# solderingtest.net
KiCad netlist of a schematic drawn in EAGLE
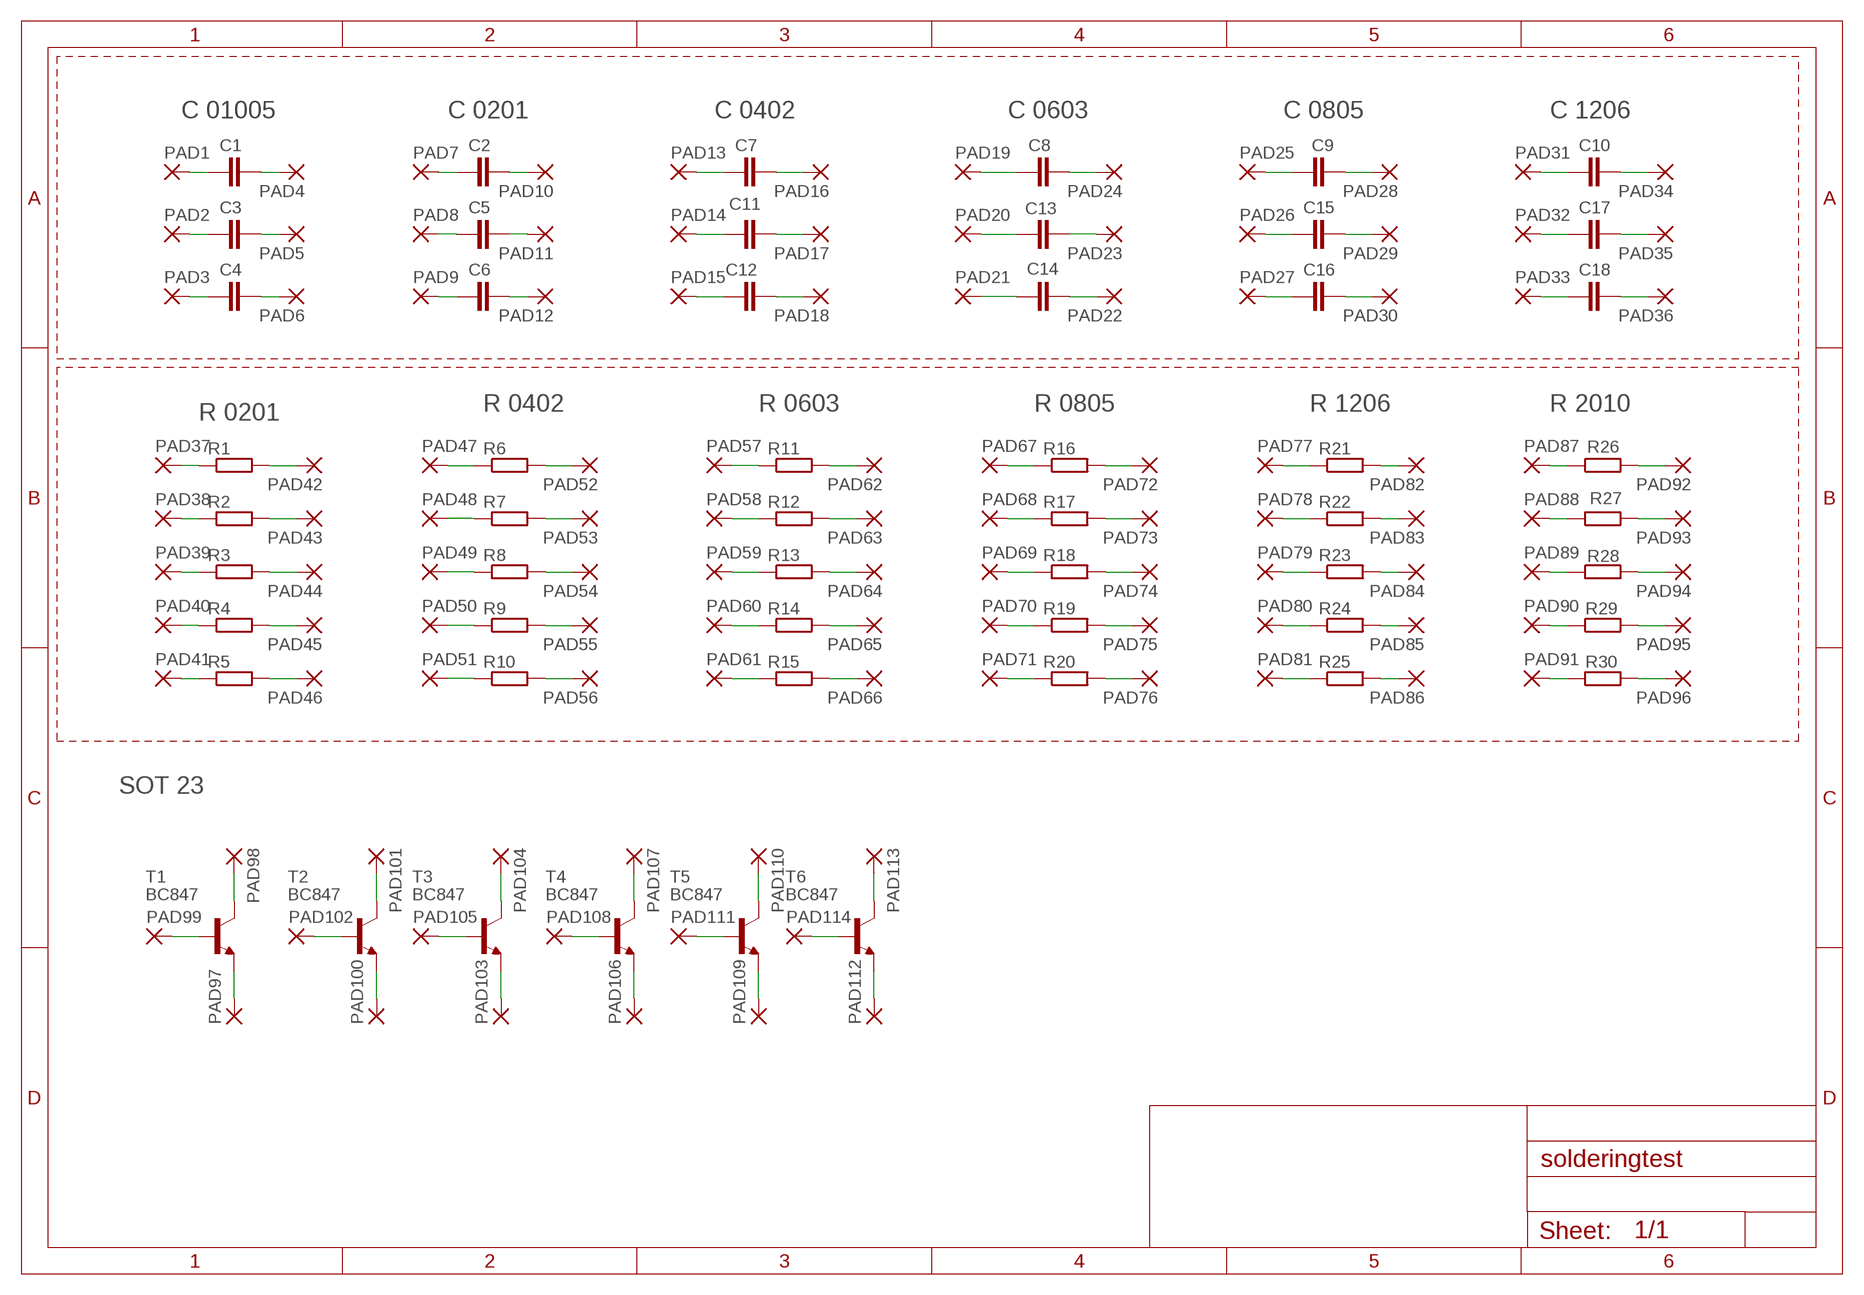
[diagram p0: schematic, sheet 1]

(export (version "E")
  (design (tool "Eeschema 10.0.6"))
  (components
    (comp (ref "C1")
      (value "C-EU01005")
      (footprint "eagle-import:C01005")
      (libsource (lib "eagle-import") (part "C-EU01005"))
    )
    (comp (ref "C2")
      (value "C-EUC0201")
      (footprint "eagle-import:C0201")
      (libsource (lib "eagle-import") (part "C-EUC0201"))
    )
    (comp (ref "C3")
      (value "C-EU01005")
      (footprint "eagle-import:C01005")
      (libsource (lib "eagle-import") (part "C-EU01005"))
    )
    (comp (ref "C4")
      (value "C-EU01005")
      (footprint "eagle-import:C01005")
      (libsource (lib "eagle-import") (part "C-EU01005"))
    )
    (comp (ref "C5")
      (value "C-EUC0201")
      (footprint "eagle-import:C0201")
      (libsource (lib "eagle-import") (part "C-EUC0201"))
    )
    (comp (ref "C6")
      (value "C-EUC0201")
      (footprint "eagle-import:C0201")
      (libsource (lib "eagle-import") (part "C-EUC0201"))
    )
    (comp (ref "C7")
      (value "C-EUC0402")
      (footprint "eagle-import:C0402")
      (libsource (lib "eagle-import") (part "C-EUC0402"))
    )
    (comp (ref "C8")
      (value "C-EUC0603")
      (footprint "eagle-import:C0603")
      (libsource (lib "eagle-import") (part "C-EUC0603"))
    )
    (comp (ref "C9")
      (value "C-EUC0805")
      (footprint "eagle-import:C0805")
      (libsource (lib "eagle-import") (part "C-EUC0805"))
    )
    (comp (ref "C10")
      (value "C-EUC1206")
      (footprint "eagle-import:C1206")
      (libsource (lib "eagle-import") (part "C-EUC1206"))
    )
    (comp (ref "C11")
      (value "C-EUC0402")
      (footprint "eagle-import:C0402")
      (libsource (lib "eagle-import") (part "C-EUC0402"))
    )
    (comp (ref "C12")
      (value "C-EUC0402")
      (footprint "eagle-import:C0402")
      (libsource (lib "eagle-import") (part "C-EUC0402"))
    )
    (comp (ref "C13")
      (value "C-EUC0603")
      (footprint "eagle-import:C0603")
      (libsource (lib "eagle-import") (part "C-EUC0603"))
    )
    (comp (ref "C14")
      (value "C-EUC0603")
      (footprint "eagle-import:C0603")
      (libsource (lib "eagle-import") (part "C-EUC0603"))
    )
    (comp (ref "C15")
      (value "C-EUC0805")
      (footprint "eagle-import:C0805")
      (libsource (lib "eagle-import") (part "C-EUC0805"))
    )
    (comp (ref "C16")
      (value "C-EUC0805")
      (footprint "eagle-import:C0805")
      (libsource (lib "eagle-import") (part "C-EUC0805"))
    )
    (comp (ref "C17")
      (value "C-EUC1206")
      (footprint "eagle-import:C1206")
      (libsource (lib "eagle-import") (part "C-EUC1206"))
    )
    (comp (ref "C18")
      (value "C-EUC1206")
      (footprint "eagle-import:C1206")
      (libsource (lib "eagle-import") (part "C-EUC1206"))
    )
    (comp (ref "PAD1")
      (value "2,54/1,0")
      (footprint "eagle-import:2,54_1,0")
      (libsource (lib "eagle-import") (part "2,54/1,0"))
    )
    (comp (ref "PAD2")
      (value "2,54/1,0")
      (footprint "eagle-import:2,54_1,0")
      (libsource (lib "eagle-import") (part "2,54/1,0"))
    )
    (comp (ref "PAD3")
      (value "2,54/1,0")
      (footprint "eagle-import:2,54_1,0")
      (libsource (lib "eagle-import") (part "2,54/1,0"))
    )
    (comp (ref "PAD4")
      (value "2,54/1,0")
      (footprint "eagle-import:2,54_1,0")
      (libsource (lib "eagle-import") (part "2,54/1,0"))
    )
    (comp (ref "PAD5")
      (value "2,54/1,0")
      (footprint "eagle-import:2,54_1,0")
      (libsource (lib "eagle-import") (part "2,54/1,0"))
    )
    (comp (ref "PAD6")
      (value "2,54/1,0")
      (footprint "eagle-import:2,54_1,0")
      (libsource (lib "eagle-import") (part "2,54/1,0"))
    )
    (comp (ref "PAD7")
      (value "2,54/1,0")
      (footprint "eagle-import:2,54_1,0")
      (libsource (lib "eagle-import") (part "2,54/1,0"))
    )
    (comp (ref "PAD8")
      (value "2,54/1,0")
      (footprint "eagle-import:2,54_1,0")
      (libsource (lib "eagle-import") (part "2,54/1,0"))
    )
    (comp (ref "PAD9")
      (value "2,54/1,0")
      (footprint "eagle-import:2,54_1,0")
      (libsource (lib "eagle-import") (part "2,54/1,0"))
    )
    (comp (ref "PAD10")
      (value "2,54/1,0")
      (footprint "eagle-import:2,54_1,0")
      (libsource (lib "eagle-import") (part "2,54/1,0"))
    )
    (comp (ref "PAD11")
      (value "2,54/1,0")
      (footprint "eagle-import:2,54_1,0")
      (libsource (lib "eagle-import") (part "2,54/1,0"))
    )
    (comp (ref "PAD12")
      (value "2,54/1,0")
      (footprint "eagle-import:2,54_1,0")
      (libsource (lib "eagle-import") (part "2,54/1,0"))
    )
    (comp (ref "PAD13")
      (value "2,54/1,0")
      (footprint "eagle-import:2,54_1,0")
      (libsource (lib "eagle-import") (part "2,54/1,0"))
    )
    (comp (ref "PAD14")
      (value "2,54/1,0")
      (footprint "eagle-import:2,54_1,0")
      (libsource (lib "eagle-import") (part "2,54/1,0"))
    )
    (comp (ref "PAD15")
      (value "2,54/1,0")
      (footprint "eagle-import:2,54_1,0")
      (libsource (lib "eagle-import") (part "2,54/1,0"))
    )
    (comp (ref "PAD16")
      (value "2,54/1,0")
      (footprint "eagle-import:2,54_1,0")
      (libsource (lib "eagle-import") (part "2,54/1,0"))
    )
    (comp (ref "PAD17")
      (value "2,54/1,0")
      (footprint "eagle-import:2,54_1,0")
      (libsource (lib "eagle-import") (part "2,54/1,0"))
    )
    (comp (ref "PAD18")
      (value "2,54/1,0")
      (footprint "eagle-import:2,54_1,0")
      (libsource (lib "eagle-import") (part "2,54/1,0"))
    )
    (comp (ref "PAD19")
      (value "2,54/1,0")
      (footprint "eagle-import:2,54_1,0")
      (libsource (lib "eagle-import") (part "2,54/1,0"))
    )
    (comp (ref "PAD20")
      (value "2,54/1,0")
      (footprint "eagle-import:2,54_1,0")
      (libsource (lib "eagle-import") (part "2,54/1,0"))
    )
    (comp (ref "PAD21")
      (value "2,54/1,0")
      (footprint "eagle-import:2,54_1,0")
      (libsource (lib "eagle-import") (part "2,54/1,0"))
    )
    (comp (ref "PAD22")
      (value "2,54/1,0")
      (footprint "eagle-import:2,54_1,0")
      (libsource (lib "eagle-import") (part "2,54/1,0"))
    )
    (comp (ref "PAD23")
      (value "2,54/1,0")
      (footprint "eagle-import:2,54_1,0")
      (libsource (lib "eagle-import") (part "2,54/1,0"))
    )
    (comp (ref "PAD24")
      (value "2,54/1,0")
      (footprint "eagle-import:2,54_1,0")
      (libsource (lib "eagle-import") (part "2,54/1,0"))
    )
    (comp (ref "PAD25")
      (value "2,54/1,0")
      (footprint "eagle-import:2,54_1,0")
      (libsource (lib "eagle-import") (part "2,54/1,0"))
    )
    (comp (ref "PAD26")
      (value "2,54/1,0")
      (footprint "eagle-import:2,54_1,0")
      (libsource (lib "eagle-import") (part "2,54/1,0"))
    )
    (comp (ref "PAD27")
      (value "2,54/1,0")
      (footprint "eagle-import:2,54_1,0")
      (libsource (lib "eagle-import") (part "2,54/1,0"))
    )
    (comp (ref "PAD28")
      (value "2,54/1,0")
      (footprint "eagle-import:2,54_1,0")
      (libsource (lib "eagle-import") (part "2,54/1,0"))
    )
    (comp (ref "PAD29")
      (value "2,54/1,0")
      (footprint "eagle-import:2,54_1,0")
      (libsource (lib "eagle-import") (part "2,54/1,0"))
    )
    (comp (ref "PAD30")
      (value "2,54/1,0")
      (footprint "eagle-import:2,54_1,0")
      (libsource (lib "eagle-import") (part "2,54/1,0"))
    )
    (comp (ref "PAD31")
      (value "2,54/1,0")
      (footprint "eagle-import:2,54_1,0")
      (libsource (lib "eagle-import") (part "2,54/1,0"))
    )
    (comp (ref "PAD32")
      (value "2,54/1,0")
      (footprint "eagle-import:2,54_1,0")
      (libsource (lib "eagle-import") (part "2,54/1,0"))
    )
    (comp (ref "PAD33")
      (value "2,54/1,0")
      (footprint "eagle-import:2,54_1,0")
      (libsource (lib "eagle-import") (part "2,54/1,0"))
    )
    (comp (ref "PAD34")
      (value "2,54/1,0")
      (footprint "eagle-import:2,54_1,0")
      (libsource (lib "eagle-import") (part "2,54/1,0"))
    )
    (comp (ref "PAD35")
      (value "2,54/1,0")
      (footprint "eagle-import:2,54_1,0")
      (libsource (lib "eagle-import") (part "2,54/1,0"))
    )
    (comp (ref "PAD36")
      (value "2,54/1,0")
      (footprint "eagle-import:2,54_1,0")
      (libsource (lib "eagle-import") (part "2,54/1,0"))
    )
    (comp (ref "PAD37")
      (value "2,54/1,0")
      (footprint "eagle-import:2,54_1,0")
      (libsource (lib "eagle-import") (part "2,54/1,0"))
    )
    (comp (ref "PAD38")
      (value "2,54/1,0")
      (footprint "eagle-import:2,54_1,0")
      (libsource (lib "eagle-import") (part "2,54/1,0"))
    )
    (comp (ref "PAD39")
      (value "2,54/1,0")
      (footprint "eagle-import:2,54_1,0")
      (libsource (lib "eagle-import") (part "2,54/1,0"))
    )
    (comp (ref "PAD40")
      (value "2,54/1,0")
      (footprint "eagle-import:2,54_1,0")
      (libsource (lib "eagle-import") (part "2,54/1,0"))
    )
    (comp (ref "PAD41")
      (value "2,54/1,0")
      (footprint "eagle-import:2,54_1,0")
      (libsource (lib "eagle-import") (part "2,54/1,0"))
    )
    (comp (ref "PAD42")
      (value "2,54/1,0")
      (footprint "eagle-import:2,54_1,0")
      (libsource (lib "eagle-import") (part "2,54/1,0"))
    )
    (comp (ref "PAD43")
      (value "2,54/1,0")
      (footprint "eagle-import:2,54_1,0")
      (libsource (lib "eagle-import") (part "2,54/1,0"))
    )
    (comp (ref "PAD44")
      (value "2,54/1,0")
      (footprint "eagle-import:2,54_1,0")
      (libsource (lib "eagle-import") (part "2,54/1,0"))
    )
    (comp (ref "PAD45")
      (value "2,54/1,0")
      (footprint "eagle-import:2,54_1,0")
      (libsource (lib "eagle-import") (part "2,54/1,0"))
    )
    (comp (ref "PAD46")
      (value "2,54/1,0")
      (footprint "eagle-import:2,54_1,0")
      (libsource (lib "eagle-import") (part "2,54/1,0"))
    )
    (comp (ref "PAD47")
      (value "2,54/1,0")
      (footprint "eagle-import:2,54_1,0")
      (libsource (lib "eagle-import") (part "2,54/1,0"))
    )
    (comp (ref "PAD48")
      (value "2,54/1,0")
      (footprint "eagle-import:2,54_1,0")
      (libsource (lib "eagle-import") (part "2,54/1,0"))
    )
    (comp (ref "PAD49")
      (value "2,54/1,0")
      (footprint "eagle-import:2,54_1,0")
      (libsource (lib "eagle-import") (part "2,54/1,0"))
    )
    (comp (ref "PAD50")
      (value "2,54/1,0")
      (footprint "eagle-import:2,54_1,0")
      (libsource (lib "eagle-import") (part "2,54/1,0"))
    )
    (comp (ref "PAD51")
      (value "2,54/1,0")
      (footprint "eagle-import:2,54_1,0")
      (libsource (lib "eagle-import") (part "2,54/1,0"))
    )
    (comp (ref "PAD52")
      (value "2,54/1,0")
      (footprint "eagle-import:2,54_1,0")
      (libsource (lib "eagle-import") (part "2,54/1,0"))
    )
    (comp (ref "PAD53")
      (value "2,54/1,0")
      (footprint "eagle-import:2,54_1,0")
      (libsource (lib "eagle-import") (part "2,54/1,0"))
    )
    (comp (ref "PAD54")
      (value "2,54/1,0")
      (footprint "eagle-import:2,54_1,0")
      (libsource (lib "eagle-import") (part "2,54/1,0"))
    )
    (comp (ref "PAD55")
      (value "2,54/1,0")
      (footprint "eagle-import:2,54_1,0")
      (libsource (lib "eagle-import") (part "2,54/1,0"))
    )
    (comp (ref "PAD56")
      (value "2,54/1,0")
      (footprint "eagle-import:2,54_1,0")
      (libsource (lib "eagle-import") (part "2,54/1,0"))
    )
    (comp (ref "PAD57")
      (value "2,54/1,0")
      (footprint "eagle-import:2,54_1,0")
      (libsource (lib "eagle-import") (part "2,54/1,0"))
    )
    (comp (ref "PAD58")
      (value "2,54/1,0")
      (footprint "eagle-import:2,54_1,0")
      (libsource (lib "eagle-import") (part "2,54/1,0"))
    )
    (comp (ref "PAD59")
      (value "2,54/1,0")
      (footprint "eagle-import:2,54_1,0")
      (libsource (lib "eagle-import") (part "2,54/1,0"))
    )
    (comp (ref "PAD60")
      (value "2,54/1,0")
      (footprint "eagle-import:2,54_1,0")
      (libsource (lib "eagle-import") (part "2,54/1,0"))
    )
    (comp (ref "PAD61")
      (value "2,54/1,0")
      (footprint "eagle-import:2,54_1,0")
      (libsource (lib "eagle-import") (part "2,54/1,0"))
    )
    (comp (ref "PAD62")
      (value "2,54/1,0")
      (footprint "eagle-import:2,54_1,0")
      (libsource (lib "eagle-import") (part "2,54/1,0"))
    )
    (comp (ref "PAD63")
      (value "2,54/1,0")
      (footprint "eagle-import:2,54_1,0")
      (libsource (lib "eagle-import") (part "2,54/1,0"))
    )
    (comp (ref "PAD64")
      (value "2,54/1,0")
      (footprint "eagle-import:2,54_1,0")
      (libsource (lib "eagle-import") (part "2,54/1,0"))
    )
    (comp (ref "PAD65")
      (value "2,54/1,0")
      (footprint "eagle-import:2,54_1,0")
      (libsource (lib "eagle-import") (part "2,54/1,0"))
    )
    (comp (ref "PAD66")
      (value "2,54/1,0")
      (footprint "eagle-import:2,54_1,0")
      (libsource (lib "eagle-import") (part "2,54/1,0"))
    )
    (comp (ref "PAD67")
      (value "2,54/1,0")
      (footprint "eagle-import:2,54_1,0")
      (libsource (lib "eagle-import") (part "2,54/1,0"))
    )
    (comp (ref "PAD68")
      (value "2,54/1,0")
      (footprint "eagle-import:2,54_1,0")
      (libsource (lib "eagle-import") (part "2,54/1,0"))
    )
    (comp (ref "PAD69")
      (value "2,54/1,0")
      (footprint "eagle-import:2,54_1,0")
      (libsource (lib "eagle-import") (part "2,54/1,0"))
    )
    (comp (ref "PAD70")
      (value "2,54/1,0")
      (footprint "eagle-import:2,54_1,0")
      (libsource (lib "eagle-import") (part "2,54/1,0"))
    )
    (comp (ref "PAD71")
      (value "2,54/1,0")
      (footprint "eagle-import:2,54_1,0")
      (libsource (lib "eagle-import") (part "2,54/1,0"))
    )
    (comp (ref "PAD72")
      (value "2,54/1,0")
      (footprint "eagle-import:2,54_1,0")
      (libsource (lib "eagle-import") (part "2,54/1,0"))
    )
    (comp (ref "PAD73")
      (value "2,54/1,0")
      (footprint "eagle-import:2,54_1,0")
      (libsource (lib "eagle-import") (part "2,54/1,0"))
    )
    (comp (ref "PAD74")
      (value "2,54/1,0")
      (footprint "eagle-import:2,54_1,0")
      (libsource (lib "eagle-import") (part "2,54/1,0"))
    )
    (comp (ref "PAD75")
      (value "2,54/1,0")
      (footprint "eagle-import:2,54_1,0")
      (libsource (lib "eagle-import") (part "2,54/1,0"))
    )
    (comp (ref "PAD76")
      (value "2,54/1,0")
      (footprint "eagle-import:2,54_1,0")
      (libsource (lib "eagle-import") (part "2,54/1,0"))
    )
    (comp (ref "PAD77")
      (value "2,54/1,0")
      (footprint "eagle-import:2,54_1,0")
      (libsource (lib "eagle-import") (part "2,54/1,0"))
    )
    (comp (ref "PAD78")
      (value "2,54/1,0")
      (footprint "eagle-import:2,54_1,0")
      (libsource (lib "eagle-import") (part "2,54/1,0"))
    )
    (comp (ref "PAD79")
      (value "2,54/1,0")
      (footprint "eagle-import:2,54_1,0")
      (libsource (lib "eagle-import") (part "2,54/1,0"))
    )
    (comp (ref "PAD80")
      (value "2,54/1,0")
      (footprint "eagle-import:2,54_1,0")
      (libsource (lib "eagle-import") (part "2,54/1,0"))
    )
    (comp (ref "PAD81")
      (value "2,54/1,0")
      (footprint "eagle-import:2,54_1,0")
      (libsource (lib "eagle-import") (part "2,54/1,0"))
    )
    (comp (ref "PAD82")
      (value "2,54/1,0")
      (footprint "eagle-import:2,54_1,0")
      (libsource (lib "eagle-import") (part "2,54/1,0"))
    )
    (comp (ref "PAD83")
      (value "2,54/1,0")
      (footprint "eagle-import:2,54_1,0")
      (libsource (lib "eagle-import") (part "2,54/1,0"))
    )
    (comp (ref "PAD84")
      (value "2,54/1,0")
      (footprint "eagle-import:2,54_1,0")
      (libsource (lib "eagle-import") (part "2,54/1,0"))
    )
    (comp (ref "PAD85")
      (value "2,54/1,0")
      (footprint "eagle-import:2,54_1,0")
      (libsource (lib "eagle-import") (part "2,54/1,0"))
    )
    (comp (ref "PAD86")
      (value "2,54/1,0")
      (footprint "eagle-import:2,54_1,0")
      (libsource (lib "eagle-import") (part "2,54/1,0"))
    )
    (comp (ref "PAD87")
      (value "2,54/1,0")
      (footprint "eagle-import:2,54_1,0")
      (libsource (lib "eagle-import") (part "2,54/1,0"))
    )
    (comp (ref "PAD88")
      (value "2,54/1,0")
      (footprint "eagle-import:2,54_1,0")
      (libsource (lib "eagle-import") (part "2,54/1,0"))
    )
    (comp (ref "PAD89")
      (value "2,54/1,0")
      (footprint "eagle-import:2,54_1,0")
      (libsource (lib "eagle-import") (part "2,54/1,0"))
    )
    (comp (ref "PAD90")
      (value "2,54/1,0")
      (footprint "eagle-import:2,54_1,0")
      (libsource (lib "eagle-import") (part "2,54/1,0"))
    )
    (comp (ref "PAD91")
      (value "2,54/1,0")
      (footprint "eagle-import:2,54_1,0")
      (libsource (lib "eagle-import") (part "2,54/1,0"))
    )
    (comp (ref "PAD92")
      (value "2,54/1,0")
      (footprint "eagle-import:2,54_1,0")
      (libsource (lib "eagle-import") (part "2,54/1,0"))
    )
    (comp (ref "PAD93")
      (value "2,54/1,0")
      (footprint "eagle-import:2,54_1,0")
      (libsource (lib "eagle-import") (part "2,54/1,0"))
    )
    (comp (ref "PAD94")
      (value "2,54/1,0")
      (footprint "eagle-import:2,54_1,0")
      (libsource (lib "eagle-import") (part "2,54/1,0"))
    )
    (comp (ref "PAD95")
      (value "2,54/1,0")
      (footprint "eagle-import:2,54_1,0")
      (libsource (lib "eagle-import") (part "2,54/1,0"))
    )
    (comp (ref "PAD96")
      (value "2,54/1,0")
      (footprint "eagle-import:2,54_1,0")
      (libsource (lib "eagle-import") (part "2,54/1,0"))
    )
    (comp (ref "PAD97")
      (value "2,54/1,0")
      (footprint "eagle-import:2,54_1,0")
      (libsource (lib "eagle-import") (part "2,54/1,0"))
    )
    (comp (ref "PAD98")
      (value "2,54/1,0")
      (footprint "eagle-import:2,54_1,0")
      (libsource (lib "eagle-import") (part "2,54/1,0"))
    )
    (comp (ref "PAD99")
      (value "2,54/1,0")
      (footprint "eagle-import:2,54_1,0")
      (libsource (lib "eagle-import") (part "2,54/1,0"))
    )
    (comp (ref "PAD100")
      (value "2,54/1,0")
      (footprint "eagle-import:2,54_1,0")
      (libsource (lib "eagle-import") (part "2,54/1,0"))
    )
    (comp (ref "PAD101")
      (value "2,54/1,0")
      (footprint "eagle-import:2,54_1,0")
      (libsource (lib "eagle-import") (part "2,54/1,0"))
    )
    (comp (ref "PAD102")
      (value "2,54/1,0")
      (footprint "eagle-import:2,54_1,0")
      (libsource (lib "eagle-import") (part "2,54/1,0"))
    )
    (comp (ref "PAD103")
      (value "2,54/1,0")
      (footprint "eagle-import:2,54_1,0")
      (libsource (lib "eagle-import") (part "2,54/1,0"))
    )
    (comp (ref "PAD104")
      (value "2,54/1,0")
      (footprint "eagle-import:2,54_1,0")
      (libsource (lib "eagle-import") (part "2,54/1,0"))
    )
    (comp (ref "PAD105")
      (value "2,54/1,0")
      (footprint "eagle-import:2,54_1,0")
      (libsource (lib "eagle-import") (part "2,54/1,0"))
    )
    (comp (ref "PAD106")
      (value "2,54/1,0")
      (footprint "eagle-import:2,54_1,0")
      (libsource (lib "eagle-import") (part "2,54/1,0"))
    )
    (comp (ref "PAD107")
      (value "2,54/1,0")
      (footprint "eagle-import:2,54_1,0")
      (libsource (lib "eagle-import") (part "2,54/1,0"))
    )
    (comp (ref "PAD108")
      (value "2,54/1,0")
      (footprint "eagle-import:2,54_1,0")
      (libsource (lib "eagle-import") (part "2,54/1,0"))
    )
    (comp (ref "PAD109")
      (value "2,54/1,0")
      (footprint "eagle-import:2,54_1,0")
      (libsource (lib "eagle-import") (part "2,54/1,0"))
    )
    (comp (ref "PAD110")
      (value "2,54/1,0")
      (footprint "eagle-import:2,54_1,0")
      (libsource (lib "eagle-import") (part "2,54/1,0"))
    )
    (comp (ref "PAD111")
      (value "2,54/1,0")
      (footprint "eagle-import:2,54_1,0")
      (libsource (lib "eagle-import") (part "2,54/1,0"))
    )
    (comp (ref "PAD112")
      (value "2,54/1,0")
      (footprint "eagle-import:2,54_1,0")
      (libsource (lib "eagle-import") (part "2,54/1,0"))
    )
    (comp (ref "PAD113")
      (value "2,54/1,0")
      (footprint "eagle-import:2,54_1,0")
      (libsource (lib "eagle-import") (part "2,54/1,0"))
    )
    (comp (ref "PAD114")
      (value "2,54/1,0")
      (footprint "eagle-import:2,54_1,0")
      (libsource (lib "eagle-import") (part "2,54/1,0"))
    )
    (comp (ref "R1")
      (value "R-EU_R0201")
      (footprint "eagle-import:R0201")
      (libsource (lib "eagle-import") (part "R-EU_R0201"))
    )
    (comp (ref "R2")
      (value "R-EU_R0201")
      (footprint "eagle-import:R0201")
      (libsource (lib "eagle-import") (part "R-EU_R0201"))
    )
    (comp (ref "R3")
      (value "R-EU_R0201")
      (footprint "eagle-import:R0201")
      (libsource (lib "eagle-import") (part "R-EU_R0201"))
    )
    (comp (ref "R4")
      (value "R-EU_R0201")
      (footprint "eagle-import:R0201")
      (libsource (lib "eagle-import") (part "R-EU_R0201"))
    )
    (comp (ref "R5")
      (value "R-EU_R0201")
      (footprint "eagle-import:R0201")
      (libsource (lib "eagle-import") (part "R-EU_R0201"))
    )
    (comp (ref "R6")
      (value "R-EU_R0402")
      (footprint "eagle-import:R0402")
      (libsource (lib "eagle-import") (part "R-EU_R0402"))
    )
    (comp (ref "R7")
      (value "R-EU_R0402")
      (footprint "eagle-import:R0402")
      (libsource (lib "eagle-import") (part "R-EU_R0402"))
    )
    (comp (ref "R8")
      (value "R-EU_R0402")
      (footprint "eagle-import:R0402")
      (libsource (lib "eagle-import") (part "R-EU_R0402"))
    )
    (comp (ref "R9")
      (value "R-EU_R0402")
      (footprint "eagle-import:R0402")
      (libsource (lib "eagle-import") (part "R-EU_R0402"))
    )
    (comp (ref "R10")
      (value "R-EU_R0402")
      (footprint "eagle-import:R0402")
      (libsource (lib "eagle-import") (part "R-EU_R0402"))
    )
    (comp (ref "R11")
      (value "R-EU_R0603")
      (footprint "eagle-import:R0603")
      (libsource (lib "eagle-import") (part "R-EU_R0603"))
    )
    (comp (ref "R12")
      (value "R-EU_R0603")
      (footprint "eagle-import:R0603")
      (libsource (lib "eagle-import") (part "R-EU_R0603"))
    )
    (comp (ref "R13")
      (value "R-EU_R0603")
      (footprint "eagle-import:R0603")
      (libsource (lib "eagle-import") (part "R-EU_R0603"))
    )
    (comp (ref "R14")
      (value "R-EU_R0603")
      (footprint "eagle-import:R0603")
      (libsource (lib "eagle-import") (part "R-EU_R0603"))
    )
    (comp (ref "R15")
      (value "R-EU_R0603")
      (footprint "eagle-import:R0603")
      (libsource (lib "eagle-import") (part "R-EU_R0603"))
    )
    (comp (ref "R16")
      (value "R-EU_R0805")
      (footprint "eagle-import:R0805")
      (libsource (lib "eagle-import") (part "R-EU_R0805"))
    )
    (comp (ref "R17")
      (value "R-EU_R0805")
      (footprint "eagle-import:R0805")
      (libsource (lib "eagle-import") (part "R-EU_R0805"))
    )
    (comp (ref "R18")
      (value "R-EU_R0805")
      (footprint "eagle-import:R0805")
      (libsource (lib "eagle-import") (part "R-EU_R0805"))
    )
    (comp (ref "R19")
      (value "R-EU_R0805")
      (footprint "eagle-import:R0805")
      (libsource (lib "eagle-import") (part "R-EU_R0805"))
    )
    (comp (ref "R20")
      (value "R-EU_R0805")
      (footprint "eagle-import:R0805")
      (libsource (lib "eagle-import") (part "R-EU_R0805"))
    )
    (comp (ref "R21")
      (value "R-EU_R1206")
      (footprint "eagle-import:R1206")
      (libsource (lib "eagle-import") (part "R-EU_R1206"))
    )
    (comp (ref "R22")
      (value "R-EU_R1206")
      (footprint "eagle-import:R1206")
      (libsource (lib "eagle-import") (part "R-EU_R1206"))
    )
    (comp (ref "R23")
      (value "R-EU_R1206")
      (footprint "eagle-import:R1206")
      (libsource (lib "eagle-import") (part "R-EU_R1206"))
    )
    (comp (ref "R24")
      (value "R-EU_R1206")
      (footprint "eagle-import:R1206")
      (libsource (lib "eagle-import") (part "R-EU_R1206"))
    )
    (comp (ref "R25")
      (value "R-EU_R1206")
      (footprint "eagle-import:R1206")
      (libsource (lib "eagle-import") (part "R-EU_R1206"))
    )
    (comp (ref "R26")
      (value "R-EU_R2010")
      (footprint "eagle-import:R2010")
      (libsource (lib "eagle-import") (part "R-EU_R2010"))
    )
    (comp (ref "R27")
      (value "R-EU_R2010")
      (footprint "eagle-import:R2010")
      (libsource (lib "eagle-import") (part "R-EU_R2010"))
    )
    (comp (ref "R28")
      (value "R-EU_R2010")
      (footprint "eagle-import:R2010")
      (libsource (lib "eagle-import") (part "R-EU_R2010"))
    )
    (comp (ref "R29")
      (value "R-EU_R2010")
      (footprint "eagle-import:R2010")
      (libsource (lib "eagle-import") (part "R-EU_R2010"))
    )
    (comp (ref "R30")
      (value "R-EU_R2010")
      (footprint "eagle-import:R2010")
      (libsource (lib "eagle-import") (part "R-EU_R2010"))
    )
    (comp (ref "T1")
      (value "BC847")
      (footprint "eagle-import:SOT23")
      (libsource (lib "eagle-import") (part "BC847"))
    )
    (comp (ref "T2")
      (value "BC847")
      (footprint "eagle-import:SOT23")
      (libsource (lib "eagle-import") (part "BC847"))
    )
    (comp (ref "T3")
      (value "BC847")
      (footprint "eagle-import:SOT23")
      (libsource (lib "eagle-import") (part "BC847"))
    )
    (comp (ref "T4")
      (value "BC847")
      (footprint "eagle-import:SOT23")
      (libsource (lib "eagle-import") (part "BC847"))
    )
    (comp (ref "T5")
      (value "BC847")
      (footprint "eagle-import:SOT23")
      (libsource (lib "eagle-import") (part "BC847"))
    )
    (comp (ref "T6")
      (value "BC847")
      (footprint "eagle-import:SOT23")
      (libsource (lib "eagle-import") (part "BC847"))
    )
  )
  (nets
    (net (code "1") (name "Net-(PAD1-P)") (class "Default")
      (node (ref "C1") (pin "1") (pinfunction "1_1") (pintype "passive"))
      (node (ref "PAD1") (pin "1") (pinfunction "P_1") (pintype "passive"))
    )
    (net (code "2") (name "Net-(PAD2-P)") (class "Default")
      (node (ref "C3") (pin "1") (pinfunction "1_1") (pintype "passive"))
      (node (ref "PAD2") (pin "1") (pinfunction "P_1") (pintype "passive"))
    )
    (net (code "3") (name "Net-(PAD3-P)") (class "Default")
      (node (ref "C4") (pin "1") (pinfunction "1_1") (pintype "passive"))
      (node (ref "PAD3") (pin "1") (pinfunction "P_1") (pintype "passive"))
    )
    (net (code "4") (name "Net-(PAD4-P)") (class "Default")
      (node (ref "C1") (pin "2") (pinfunction "2_2") (pintype "passive"))
      (node (ref "PAD4") (pin "1") (pinfunction "P_1") (pintype "passive"))
    )
    (net (code "5") (name "Net-(PAD5-P)") (class "Default")
      (node (ref "C3") (pin "2") (pinfunction "2_2") (pintype "passive"))
      (node (ref "PAD5") (pin "1") (pinfunction "P_1") (pintype "passive"))
    )
    (net (code "6") (name "Net-(PAD6-P)") (class "Default")
      (node (ref "C4") (pin "2") (pinfunction "2_2") (pintype "passive"))
      (node (ref "PAD6") (pin "1") (pinfunction "P_1") (pintype "passive"))
    )
    (net (code "7") (name "Net-(PAD7-P)") (class "Default")
      (node (ref "C2") (pin "1") (pinfunction "1_1") (pintype "passive"))
      (node (ref "PAD7") (pin "1") (pinfunction "P_1") (pintype "passive"))
    )
    (net (code "8") (name "Net-(PAD8-P)") (class "Default")
      (node (ref "C5") (pin "1") (pinfunction "1_1") (pintype "passive"))
      (node (ref "PAD8") (pin "1") (pinfunction "P_1") (pintype "passive"))
    )
    (net (code "9") (name "Net-(PAD9-P)") (class "Default")
      (node (ref "C6") (pin "1") (pinfunction "1_1") (pintype "passive"))
      (node (ref "PAD9") (pin "1") (pinfunction "P_1") (pintype "passive"))
    )
    (net (code "10") (name "Net-(PAD10-P)") (class "Default")
      (node (ref "C2") (pin "2") (pinfunction "2_2") (pintype "passive"))
      (node (ref "PAD10") (pin "1") (pinfunction "P_1") (pintype "passive"))
    )
    (net (code "11") (name "Net-(PAD11-P)") (class "Default")
      (node (ref "C5") (pin "2") (pinfunction "2_2") (pintype "passive"))
      (node (ref "PAD11") (pin "1") (pinfunction "P_1") (pintype "passive"))
    )
    (net (code "12") (name "Net-(PAD12-P)") (class "Default")
      (node (ref "C6") (pin "2") (pinfunction "2_2") (pintype "passive"))
      (node (ref "PAD12") (pin "1") (pinfunction "P_1") (pintype "passive"))
    )
    (net (code "13") (name "Net-(PAD13-P)") (class "Default")
      (node (ref "C7") (pin "1") (pinfunction "1_1") (pintype "passive"))
      (node (ref "PAD13") (pin "1") (pinfunction "P_1") (pintype "passive"))
    )
    (net (code "14") (name "Net-(PAD14-P)") (class "Default")
      (node (ref "C11") (pin "1") (pinfunction "1_1") (pintype "passive"))
      (node (ref "PAD14") (pin "1") (pinfunction "P_1") (pintype "passive"))
    )
    (net (code "15") (name "Net-(PAD15-P)") (class "Default")
      (node (ref "C12") (pin "1") (pinfunction "1_1") (pintype "passive"))
      (node (ref "PAD15") (pin "1") (pinfunction "P_1") (pintype "passive"))
    )
    (net (code "16") (name "Net-(PAD16-P)") (class "Default")
      (node (ref "C7") (pin "2") (pinfunction "2_2") (pintype "passive"))
      (node (ref "PAD16") (pin "1") (pinfunction "P_1") (pintype "passive"))
    )
    (net (code "17") (name "Net-(PAD17-P)") (class "Default")
      (node (ref "C11") (pin "2") (pinfunction "2_2") (pintype "passive"))
      (node (ref "PAD17") (pin "1") (pinfunction "P_1") (pintype "passive"))
    )
    (net (code "18") (name "Net-(PAD18-P)") (class "Default")
      (node (ref "C12") (pin "2") (pinfunction "2_2") (pintype "passive"))
      (node (ref "PAD18") (pin "1") (pinfunction "P_1") (pintype "passive"))
    )
    (net (code "19") (name "Net-(PAD19-P)") (class "Default")
      (node (ref "C8") (pin "1") (pinfunction "1_1") (pintype "passive"))
      (node (ref "PAD19") (pin "1") (pinfunction "P_1") (pintype "passive"))
    )
    (net (code "20") (name "Net-(PAD20-P)") (class "Default")
      (node (ref "C13") (pin "1") (pinfunction "1_1") (pintype "passive"))
      (node (ref "PAD20") (pin "1") (pinfunction "P_1") (pintype "passive"))
    )
    (net (code "21") (name "Net-(PAD21-P)") (class "Default")
      (node (ref "C14") (pin "1") (pinfunction "1_1") (pintype "passive"))
      (node (ref "PAD21") (pin "1") (pinfunction "P_1") (pintype "passive"))
    )
    (net (code "22") (name "Net-(PAD22-P)") (class "Default")
      (node (ref "C14") (pin "2") (pinfunction "2_2") (pintype "passive"))
      (node (ref "PAD22") (pin "1") (pinfunction "P_1") (pintype "passive"))
    )
    (net (code "23") (name "Net-(PAD23-P)") (class "Default")
      (node (ref "C13") (pin "2") (pinfunction "2_2") (pintype "passive"))
      (node (ref "PAD23") (pin "1") (pinfunction "P_1") (pintype "passive"))
    )
    (net (code "24") (name "Net-(PAD24-P)") (class "Default")
      (node (ref "C8") (pin "2") (pinfunction "2_2") (pintype "passive"))
      (node (ref "PAD24") (pin "1") (pinfunction "P_1") (pintype "passive"))
    )
    (net (code "25") (name "Net-(PAD25-P)") (class "Default")
      (node (ref "C9") (pin "1") (pinfunction "1_1") (pintype "passive"))
      (node (ref "PAD25") (pin "1") (pinfunction "P_1") (pintype "passive"))
    )
    (net (code "26") (name "Net-(PAD26-P)") (class "Default")
      (node (ref "C15") (pin "1") (pinfunction "1_1") (pintype "passive"))
      (node (ref "PAD26") (pin "1") (pinfunction "P_1") (pintype "passive"))
    )
    (net (code "27") (name "Net-(PAD27-P)") (class "Default")
      (node (ref "C16") (pin "1") (pinfunction "1_1") (pintype "passive"))
      (node (ref "PAD27") (pin "1") (pinfunction "P_1") (pintype "passive"))
    )
    (net (code "28") (name "Net-(PAD28-P)") (class "Default")
      (node (ref "C9") (pin "2") (pinfunction "2_2") (pintype "passive"))
      (node (ref "PAD28") (pin "1") (pinfunction "P_1") (pintype "passive"))
    )
    (net (code "29") (name "Net-(PAD29-P)") (class "Default")
      (node (ref "C15") (pin "2") (pinfunction "2_2") (pintype "passive"))
      (node (ref "PAD29") (pin "1") (pinfunction "P_1") (pintype "passive"))
    )
    (net (code "30") (name "Net-(PAD30-P)") (class "Default")
      (node (ref "C16") (pin "2") (pinfunction "2_2") (pintype "passive"))
      (node (ref "PAD30") (pin "1") (pinfunction "P_1") (pintype "passive"))
    )
    (net (code "31") (name "Net-(PAD31-P)") (class "Default")
      (node (ref "C10") (pin "1") (pinfunction "1_1") (pintype "passive"))
      (node (ref "PAD31") (pin "1") (pinfunction "P_1") (pintype "passive"))
    )
    (net (code "32") (name "Net-(PAD32-P)") (class "Default")
      (node (ref "C17") (pin "1") (pinfunction "1_1") (pintype "passive"))
      (node (ref "PAD32") (pin "1") (pinfunction "P_1") (pintype "passive"))
    )
    (net (code "33") (name "Net-(PAD33-P)") (class "Default")
      (node (ref "C18") (pin "1") (pinfunction "1_1") (pintype "passive"))
      (node (ref "PAD33") (pin "1") (pinfunction "P_1") (pintype "passive"))
    )
    (net (code "34") (name "Net-(PAD34-P)") (class "Default")
      (node (ref "C10") (pin "2") (pinfunction "2_2") (pintype "passive"))
      (node (ref "PAD34") (pin "1") (pinfunction "P_1") (pintype "passive"))
    )
    (net (code "35") (name "Net-(PAD35-P)") (class "Default")
      (node (ref "C17") (pin "2") (pinfunction "2_2") (pintype "passive"))
      (node (ref "PAD35") (pin "1") (pinfunction "P_1") (pintype "passive"))
    )
    (net (code "36") (name "Net-(PAD36-P)") (class "Default")
      (node (ref "C18") (pin "2") (pinfunction "2_2") (pintype "passive"))
      (node (ref "PAD36") (pin "1") (pinfunction "P_1") (pintype "passive"))
    )
    (net (code "37") (name "Net-(PAD37-P)") (class "Default")
      (node (ref "PAD37") (pin "1") (pinfunction "P_1") (pintype "passive"))
      (node (ref "R1") (pin "1") (pinfunction "1_1") (pintype "passive"))
    )
    (net (code "38") (name "Net-(PAD38-P)") (class "Default")
      (node (ref "PAD38") (pin "1") (pinfunction "P_1") (pintype "passive"))
      (node (ref "R2") (pin "1") (pinfunction "1_1") (pintype "passive"))
    )
    (net (code "39") (name "Net-(PAD39-P)") (class "Default")
      (node (ref "PAD39") (pin "1") (pinfunction "P_1") (pintype "passive"))
      (node (ref "R3") (pin "1") (pinfunction "1_1") (pintype "passive"))
    )
    (net (code "40") (name "Net-(PAD40-P)") (class "Default")
      (node (ref "PAD40") (pin "1") (pinfunction "P_1") (pintype "passive"))
      (node (ref "R4") (pin "1") (pinfunction "1_1") (pintype "passive"))
    )
    (net (code "41") (name "Net-(PAD41-P)") (class "Default")
      (node (ref "PAD41") (pin "1") (pinfunction "P_1") (pintype "passive"))
      (node (ref "R5") (pin "1") (pinfunction "1_1") (pintype "passive"))
    )
    (net (code "42") (name "Net-(PAD42-P)") (class "Default")
      (node (ref "PAD42") (pin "1") (pinfunction "P_1") (pintype "passive"))
      (node (ref "R1") (pin "2") (pinfunction "2_2") (pintype "passive"))
    )
    (net (code "43") (name "Net-(PAD43-P)") (class "Default")
      (node (ref "PAD43") (pin "1") (pinfunction "P_1") (pintype "passive"))
      (node (ref "R2") (pin "2") (pinfunction "2_2") (pintype "passive"))
    )
    (net (code "44") (name "Net-(PAD44-P)") (class "Default")
      (node (ref "PAD44") (pin "1") (pinfunction "P_1") (pintype "passive"))
      (node (ref "R3") (pin "2") (pinfunction "2_2") (pintype "passive"))
    )
    (net (code "45") (name "Net-(PAD45-P)") (class "Default")
      (node (ref "PAD45") (pin "1") (pinfunction "P_1") (pintype "passive"))
      (node (ref "R4") (pin "2") (pinfunction "2_2") (pintype "passive"))
    )
    (net (code "46") (name "Net-(PAD46-P)") (class "Default")
      (node (ref "PAD46") (pin "1") (pinfunction "P_1") (pintype "passive"))
      (node (ref "R5") (pin "2") (pinfunction "2_2") (pintype "passive"))
    )
    (net (code "47") (name "Net-(PAD47-P)") (class "Default")
      (node (ref "PAD47") (pin "1") (pinfunction "P_1") (pintype "passive"))
      (node (ref "R6") (pin "1") (pinfunction "1_1") (pintype "passive"))
    )
    (net (code "48") (name "Net-(PAD48-P)") (class "Default")
      (node (ref "PAD48") (pin "1") (pinfunction "P_1") (pintype "passive"))
      (node (ref "R7") (pin "1") (pinfunction "1_1") (pintype "passive"))
    )
    (net (code "49") (name "Net-(PAD49-P)") (class "Default")
      (node (ref "PAD49") (pin "1") (pinfunction "P_1") (pintype "passive"))
      (node (ref "R8") (pin "1") (pinfunction "1_1") (pintype "passive"))
    )
    (net (code "50") (name "Net-(PAD50-P)") (class "Default")
      (node (ref "PAD50") (pin "1") (pinfunction "P_1") (pintype "passive"))
      (node (ref "R9") (pin "1") (pinfunction "1_1") (pintype "passive"))
    )
    (net (code "51") (name "Net-(PAD51-P)") (class "Default")
      (node (ref "PAD51") (pin "1") (pinfunction "P_1") (pintype "passive"))
      (node (ref "R10") (pin "1") (pinfunction "1_1") (pintype "passive"))
    )
    (net (code "52") (name "Net-(PAD52-P)") (class "Default")
      (node (ref "PAD52") (pin "1") (pinfunction "P_1") (pintype "passive"))
      (node (ref "R6") (pin "2") (pinfunction "2_2") (pintype "passive"))
    )
    (net (code "53") (name "Net-(PAD53-P)") (class "Default")
      (node (ref "PAD53") (pin "1") (pinfunction "P_1") (pintype "passive"))
      (node (ref "R7") (pin "2") (pinfunction "2_2") (pintype "passive"))
    )
    (net (code "54") (name "Net-(PAD54-P)") (class "Default")
      (node (ref "PAD54") (pin "1") (pinfunction "P_1") (pintype "passive"))
      (node (ref "R8") (pin "2") (pinfunction "2_2") (pintype "passive"))
    )
    (net (code "55") (name "Net-(PAD55-P)") (class "Default")
      (node (ref "PAD55") (pin "1") (pinfunction "P_1") (pintype "passive"))
      (node (ref "R9") (pin "2") (pinfunction "2_2") (pintype "passive"))
    )
    (net (code "56") (name "Net-(PAD56-P)") (class "Default")
      (node (ref "PAD56") (pin "1") (pinfunction "P_1") (pintype "passive"))
      (node (ref "R10") (pin "2") (pinfunction "2_2") (pintype "passive"))
    )
    (net (code "57") (name "Net-(PAD57-P)") (class "Default")
      (node (ref "PAD57") (pin "1") (pinfunction "P_1") (pintype "passive"))
      (node (ref "R11") (pin "1") (pinfunction "1_1") (pintype "passive"))
    )
    (net (code "58") (name "Net-(PAD58-P)") (class "Default")
      (node (ref "PAD58") (pin "1") (pinfunction "P_1") (pintype "passive"))
      (node (ref "R12") (pin "1") (pinfunction "1_1") (pintype "passive"))
    )
    (net (code "59") (name "Net-(PAD59-P)") (class "Default")
      (node (ref "PAD59") (pin "1") (pinfunction "P_1") (pintype "passive"))
      (node (ref "R13") (pin "1") (pinfunction "1_1") (pintype "passive"))
    )
    (net (code "60") (name "Net-(PAD60-P)") (class "Default")
      (node (ref "PAD60") (pin "1") (pinfunction "P_1") (pintype "passive"))
      (node (ref "R14") (pin "1") (pinfunction "1_1") (pintype "passive"))
    )
    (net (code "61") (name "Net-(PAD61-P)") (class "Default")
      (node (ref "PAD61") (pin "1") (pinfunction "P_1") (pintype "passive"))
      (node (ref "R15") (pin "1") (pinfunction "1_1") (pintype "passive"))
    )
    (net (code "62") (name "Net-(PAD62-P)") (class "Default")
      (node (ref "PAD62") (pin "1") (pinfunction "P_1") (pintype "passive"))
      (node (ref "R11") (pin "2") (pinfunction "2_2") (pintype "passive"))
    )
    (net (code "63") (name "Net-(PAD63-P)") (class "Default")
      (node (ref "PAD63") (pin "1") (pinfunction "P_1") (pintype "passive"))
      (node (ref "R12") (pin "2") (pinfunction "2_2") (pintype "passive"))
    )
    (net (code "64") (name "Net-(PAD64-P)") (class "Default")
      (node (ref "PAD64") (pin "1") (pinfunction "P_1") (pintype "passive"))
      (node (ref "R13") (pin "2") (pinfunction "2_2") (pintype "passive"))
    )
    (net (code "65") (name "Net-(PAD65-P)") (class "Default")
      (node (ref "PAD65") (pin "1") (pinfunction "P_1") (pintype "passive"))
      (node (ref "R14") (pin "2") (pinfunction "2_2") (pintype "passive"))
    )
    (net (code "66") (name "Net-(PAD66-P)") (class "Default")
      (node (ref "PAD66") (pin "1") (pinfunction "P_1") (pintype "passive"))
      (node (ref "R15") (pin "2") (pinfunction "2_2") (pintype "passive"))
    )
    (net (code "67") (name "Net-(PAD67-P)") (class "Default")
      (node (ref "PAD67") (pin "1") (pinfunction "P_1") (pintype "passive"))
      (node (ref "R16") (pin "1") (pinfunction "1_1") (pintype "passive"))
    )
    (net (code "68") (name "Net-(PAD68-P)") (class "Default")
      (node (ref "PAD68") (pin "1") (pinfunction "P_1") (pintype "passive"))
      (node (ref "R17") (pin "1") (pinfunction "1_1") (pintype "passive"))
    )
    (net (code "69") (name "Net-(PAD69-P)") (class "Default")
      (node (ref "PAD69") (pin "1") (pinfunction "P_1") (pintype "passive"))
      (node (ref "R18") (pin "1") (pinfunction "1_1") (pintype "passive"))
    )
    (net (code "70") (name "Net-(PAD70-P)") (class "Default")
      (node (ref "PAD70") (pin "1") (pinfunction "P_1") (pintype "passive"))
      (node (ref "R19") (pin "1") (pinfunction "1_1") (pintype "passive"))
    )
    (net (code "71") (name "Net-(PAD71-P)") (class "Default")
      (node (ref "PAD71") (pin "1") (pinfunction "P_1") (pintype "passive"))
      (node (ref "R20") (pin "1") (pinfunction "1_1") (pintype "passive"))
    )
    (net (code "72") (name "Net-(PAD72-P)") (class "Default")
      (node (ref "PAD72") (pin "1") (pinfunction "P_1") (pintype "passive"))
      (node (ref "R16") (pin "2") (pinfunction "2_2") (pintype "passive"))
    )
    (net (code "73") (name "Net-(PAD73-P)") (class "Default")
      (node (ref "PAD73") (pin "1") (pinfunction "P_1") (pintype "passive"))
      (node (ref "R17") (pin "2") (pinfunction "2_2") (pintype "passive"))
    )
    (net (code "74") (name "Net-(PAD74-P)") (class "Default")
      (node (ref "PAD74") (pin "1") (pinfunction "P_1") (pintype "passive"))
      (node (ref "R18") (pin "2") (pinfunction "2_2") (pintype "passive"))
    )
    (net (code "75") (name "Net-(PAD75-P)") (class "Default")
      (node (ref "PAD75") (pin "1") (pinfunction "P_1") (pintype "passive"))
      (node (ref "R19") (pin "2") (pinfunction "2_2") (pintype "passive"))
    )
    (net (code "76") (name "Net-(PAD76-P)") (class "Default")
      (node (ref "PAD76") (pin "1") (pinfunction "P_1") (pintype "passive"))
      (node (ref "R20") (pin "2") (pinfunction "2_2") (pintype "passive"))
    )
    (net (code "77") (name "Net-(PAD77-P)") (class "Default")
      (node (ref "PAD77") (pin "1") (pinfunction "P_1") (pintype "passive"))
      (node (ref "R21") (pin "1") (pinfunction "1_1") (pintype "passive"))
    )
    (net (code "78") (name "Net-(PAD78-P)") (class "Default")
      (node (ref "PAD78") (pin "1") (pinfunction "P_1") (pintype "passive"))
      (node (ref "R22") (pin "1") (pinfunction "1_1") (pintype "passive"))
    )
    (net (code "79") (name "Net-(PAD79-P)") (class "Default")
      (node (ref "PAD79") (pin "1") (pinfunction "P_1") (pintype "passive"))
      (node (ref "R23") (pin "1") (pinfunction "1_1") (pintype "passive"))
    )
    (net (code "80") (name "Net-(PAD80-P)") (class "Default")
      (node (ref "PAD80") (pin "1") (pinfunction "P_1") (pintype "passive"))
      (node (ref "R24") (pin "1") (pinfunction "1_1") (pintype "passive"))
    )
    (net (code "81") (name "Net-(PAD81-P)") (class "Default")
      (node (ref "PAD81") (pin "1") (pinfunction "P_1") (pintype "passive"))
      (node (ref "R25") (pin "1") (pinfunction "1_1") (pintype "passive"))
    )
    (net (code "82") (name "Net-(PAD82-P)") (class "Default")
      (node (ref "PAD82") (pin "1") (pinfunction "P_1") (pintype "passive"))
      (node (ref "R21") (pin "2") (pinfunction "2_2") (pintype "passive"))
    )
    (net (code "83") (name "Net-(PAD83-P)") (class "Default")
      (node (ref "PAD83") (pin "1") (pinfunction "P_1") (pintype "passive"))
      (node (ref "R22") (pin "2") (pinfunction "2_2") (pintype "passive"))
    )
    (net (code "84") (name "Net-(PAD84-P)") (class "Default")
      (node (ref "PAD84") (pin "1") (pinfunction "P_1") (pintype "passive"))
      (node (ref "R23") (pin "2") (pinfunction "2_2") (pintype "passive"))
    )
    (net (code "85") (name "Net-(PAD85-P)") (class "Default")
      (node (ref "PAD85") (pin "1") (pinfunction "P_1") (pintype "passive"))
      (node (ref "R24") (pin "2") (pinfunction "2_2") (pintype "passive"))
    )
    (net (code "86") (name "Net-(PAD86-P)") (class "Default")
      (node (ref "PAD86") (pin "1") (pinfunction "P_1") (pintype "passive"))
      (node (ref "R25") (pin "2") (pinfunction "2_2") (pintype "passive"))
    )
    (net (code "87") (name "Net-(PAD87-P)") (class "Default")
      (node (ref "PAD87") (pin "1") (pinfunction "P_1") (pintype "passive"))
      (node (ref "R26") (pin "1") (pinfunction "1_1") (pintype "passive"))
    )
    (net (code "88") (name "Net-(PAD88-P)") (class "Default")
      (node (ref "PAD88") (pin "1") (pinfunction "P_1") (pintype "passive"))
      (node (ref "R27") (pin "1") (pinfunction "1_1") (pintype "passive"))
    )
    (net (code "89") (name "Net-(PAD89-P)") (class "Default")
      (node (ref "PAD89") (pin "1") (pinfunction "P_1") (pintype "passive"))
      (node (ref "R28") (pin "1") (pinfunction "1_1") (pintype "passive"))
    )
    (net (code "90") (name "Net-(PAD90-P)") (class "Default")
      (node (ref "PAD90") (pin "1") (pinfunction "P_1") (pintype "passive"))
      (node (ref "R29") (pin "1") (pinfunction "1_1") (pintype "passive"))
    )
    (net (code "91") (name "Net-(PAD91-P)") (class "Default")
      (node (ref "PAD91") (pin "1") (pinfunction "P_1") (pintype "passive"))
      (node (ref "R30") (pin "1") (pinfunction "1_1") (pintype "passive"))
    )
    (net (code "92") (name "Net-(PAD92-P)") (class "Default")
      (node (ref "PAD92") (pin "1") (pinfunction "P_1") (pintype "passive"))
      (node (ref "R26") (pin "2") (pinfunction "2_2") (pintype "passive"))
    )
    (net (code "93") (name "Net-(PAD93-P)") (class "Default")
      (node (ref "PAD93") (pin "1") (pinfunction "P_1") (pintype "passive"))
      (node (ref "R27") (pin "2") (pinfunction "2_2") (pintype "passive"))
    )
    (net (code "94") (name "Net-(PAD94-P)") (class "Default")
      (node (ref "PAD94") (pin "1") (pinfunction "P_1") (pintype "passive"))
      (node (ref "R28") (pin "2") (pinfunction "2_2") (pintype "passive"))
    )
    (net (code "95") (name "Net-(PAD95-P)") (class "Default")
      (node (ref "PAD95") (pin "1") (pinfunction "P_1") (pintype "passive"))
      (node (ref "R29") (pin "2") (pinfunction "2_2") (pintype "passive"))
    )
    (net (code "96") (name "Net-(PAD96-P)") (class "Default")
      (node (ref "PAD96") (pin "1") (pinfunction "P_1") (pintype "passive"))
      (node (ref "R30") (pin "2") (pinfunction "2_2") (pintype "passive"))
    )
    (net (code "97") (name "Net-(PAD97-P)") (class "Default")
      (node (ref "PAD97") (pin "1") (pinfunction "P_1") (pintype "passive"))
      (node (ref "T1") (pin "2") (pinfunction "E_2") (pintype "passive"))
    )
    (net (code "98") (name "Net-(PAD98-P)") (class "Default")
      (node (ref "PAD98") (pin "1") (pinfunction "P_1") (pintype "passive"))
      (node (ref "T1") (pin "3") (pinfunction "C_3") (pintype "passive"))
    )
    (net (code "99") (name "Net-(PAD99-P)") (class "Default")
      (node (ref "PAD99") (pin "1") (pinfunction "P_1") (pintype "passive"))
      (node (ref "T1") (pin "1") (pinfunction "B_1") (pintype "passive"))
    )
    (net (code "100") (name "Net-(PAD100-P)") (class "Default")
      (node (ref "PAD100") (pin "1") (pinfunction "P_1") (pintype "passive"))
      (node (ref "T2") (pin "2") (pinfunction "E_2") (pintype "passive"))
    )
    (net (code "101") (name "Net-(PAD101-P)") (class "Default")
      (node (ref "PAD101") (pin "1") (pinfunction "P_1") (pintype "passive"))
      (node (ref "T2") (pin "3") (pinfunction "C_3") (pintype "passive"))
    )
    (net (code "102") (name "Net-(PAD102-P)") (class "Default")
      (node (ref "PAD102") (pin "1") (pinfunction "P_1") (pintype "passive"))
      (node (ref "T2") (pin "1") (pinfunction "B_1") (pintype "passive"))
    )
    (net (code "103") (name "Net-(PAD103-P)") (class "Default")
      (node (ref "PAD103") (pin "1") (pinfunction "P_1") (pintype "passive"))
      (node (ref "T3") (pin "2") (pinfunction "E_2") (pintype "passive"))
    )
    (net (code "104") (name "Net-(PAD104-P)") (class "Default")
      (node (ref "PAD104") (pin "1") (pinfunction "P_1") (pintype "passive"))
      (node (ref "T3") (pin "3") (pinfunction "C_3") (pintype "passive"))
    )
    (net (code "105") (name "Net-(PAD105-P)") (class "Default")
      (node (ref "PAD105") (pin "1") (pinfunction "P_1") (pintype "passive"))
      (node (ref "T3") (pin "1") (pinfunction "B_1") (pintype "passive"))
    )
    (net (code "106") (name "Net-(PAD106-P)") (class "Default")
      (node (ref "PAD106") (pin "1") (pinfunction "P_1") (pintype "passive"))
      (node (ref "T4") (pin "2") (pinfunction "E_2") (pintype "passive"))
    )
    (net (code "107") (name "Net-(PAD107-P)") (class "Default")
      (node (ref "PAD107") (pin "1") (pinfunction "P_1") (pintype "passive"))
      (node (ref "T4") (pin "3") (pinfunction "C_3") (pintype "passive"))
    )
    (net (code "108") (name "Net-(PAD108-P)") (class "Default")
      (node (ref "PAD108") (pin "1") (pinfunction "P_1") (pintype "passive"))
      (node (ref "T4") (pin "1") (pinfunction "B_1") (pintype "passive"))
    )
    (net (code "109") (name "Net-(PAD109-P)") (class "Default")
      (node (ref "PAD109") (pin "1") (pinfunction "P_1") (pintype "passive"))
      (node (ref "T5") (pin "2") (pinfunction "E_2") (pintype "passive"))
    )
    (net (code "110") (name "Net-(PAD110-P)") (class "Default")
      (node (ref "PAD110") (pin "1") (pinfunction "P_1") (pintype "passive"))
      (node (ref "T5") (pin "3") (pinfunction "C_3") (pintype "passive"))
    )
    (net (code "111") (name "Net-(PAD111-P)") (class "Default")
      (node (ref "PAD111") (pin "1") (pinfunction "P_1") (pintype "passive"))
      (node (ref "T5") (pin "1") (pinfunction "B_1") (pintype "passive"))
    )
    (net (code "112") (name "Net-(PAD112-P)") (class "Default")
      (node (ref "PAD112") (pin "1") (pinfunction "P_1") (pintype "passive"))
      (node (ref "T6") (pin "2") (pinfunction "E_2") (pintype "passive"))
    )
    (net (code "113") (name "Net-(PAD113-P)") (class "Default")
      (node (ref "PAD113") (pin "1") (pinfunction "P_1") (pintype "passive"))
      (node (ref "T6") (pin "3") (pinfunction "C_3") (pintype "passive"))
    )
    (net (code "114") (name "Net-(PAD114-P)") (class "Default")
      (node (ref "PAD114") (pin "1") (pinfunction "P_1") (pintype "passive"))
      (node (ref "T6") (pin "1") (pinfunction "B_1") (pintype "passive"))
    )
  )
)
